# rw-pd1b.net
KiCad netlist of a schematic drawn in EAGLE
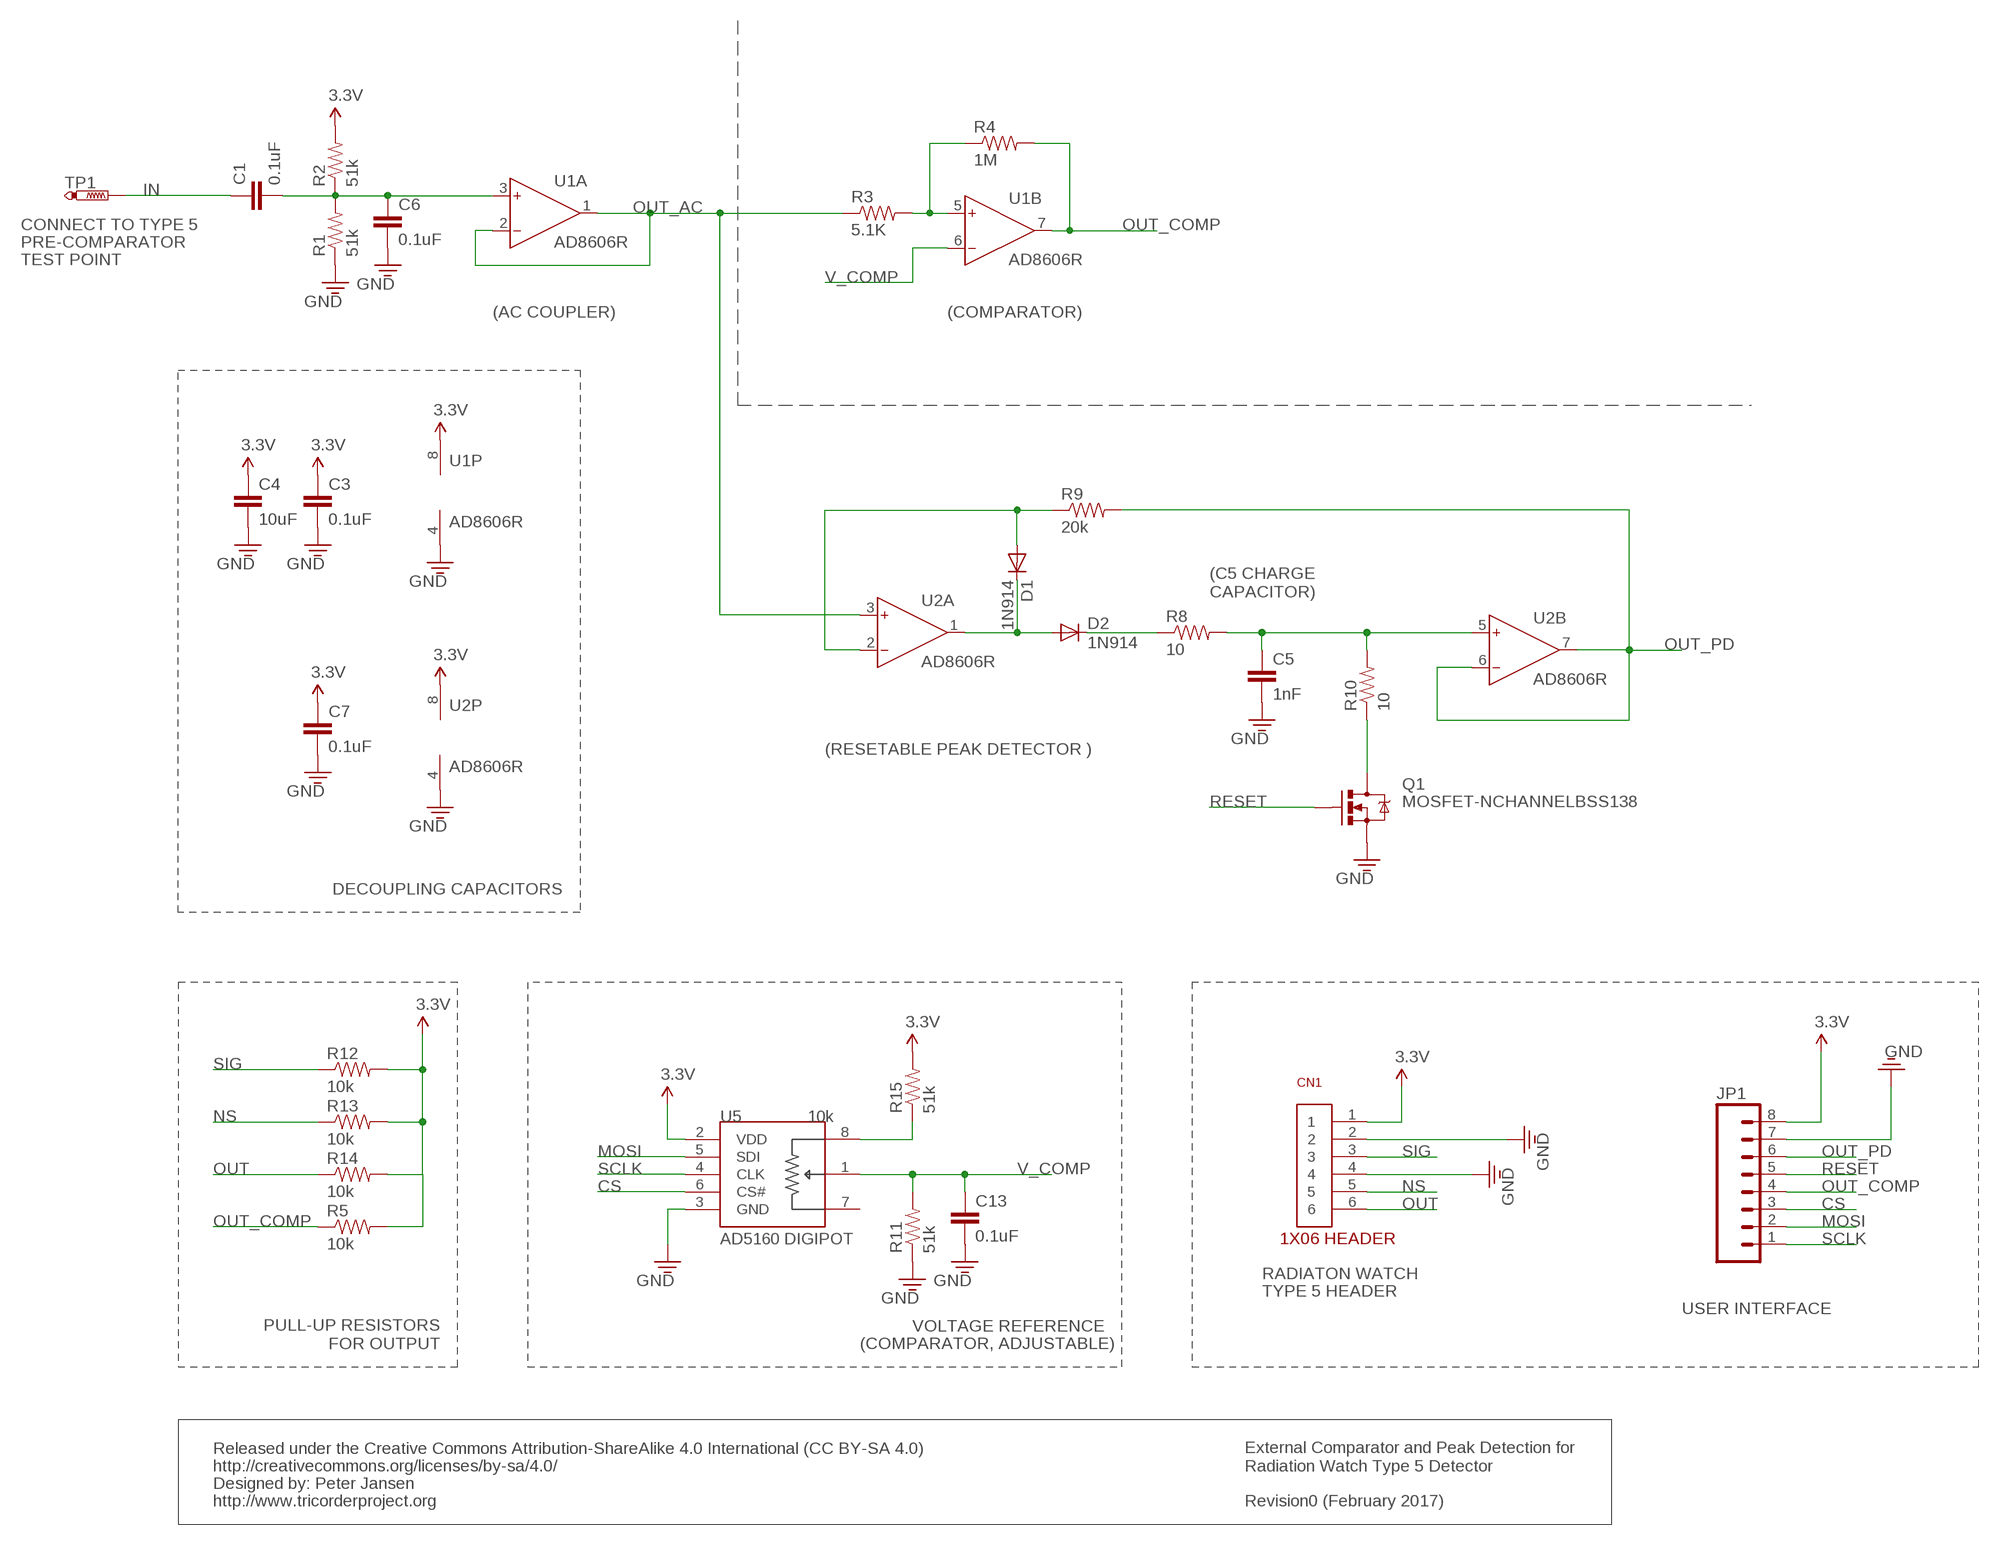
[diagram p0: schematic, sheet 1]

(export (version "E")
  (design (tool "Eeschema 10.0.6"))
  (components
    (comp (ref "C1")
      (value "0.1uF")
      (footprint "eagle-import:0603")
      (libsource (lib "eagle-import") (part "CAP0603"))
    )
    (comp (ref "C3")
      (value "0.1uF")
      (footprint "eagle-import:0603")
      (libsource (lib "eagle-import") (part "CAP0603"))
    )
    (comp (ref "C4")
      (value "10uF")
      (footprint "eagle-import:0603")
      (libsource (lib "eagle-import") (part "CAP0603"))
    )
    (comp (ref "C5")
      (value "1nF")
      (footprint "eagle-import:0603")
      (libsource (lib "eagle-import") (part "CAP0603"))
    )
    (comp (ref "C6")
      (value "0.1uF")
      (footprint "eagle-import:0603")
      (libsource (lib "eagle-import") (part "CAP0603"))
    )
    (comp (ref "C7")
      (value "0.1uF")
      (footprint "eagle-import:0603")
      (libsource (lib "eagle-import") (part "CAP0603"))
    )
    (comp (ref "C13")
      (value "0.1uF")
      (footprint "eagle-import:0603")
      (libsource (lib "eagle-import") (part "openct_CAP0603"))
    )
    (comp (ref "CN1")
      (value "1X06")
      (footprint "eagle-import:1X06")
      (libsource (lib "eagle-import") (part "1X06"))
    )
    (comp (ref "D1")
      (value "1N914")
      (footprint "eagle-import:SOD-323")
      (libsource (lib "eagle-import") (part "DIODESOD"))
    )
    (comp (ref "D2")
      (value "1N914")
      (footprint "eagle-import:SOD-323")
      (libsource (lib "eagle-import") (part "DIODESOD"))
    )
    (comp (ref "JP1")
      (value "M08LOCK")
      (footprint "eagle-import:1X08_LOCK")
      (libsource (lib "eagle-import") (part "M08LOCK"))
    )
    (comp (ref "Q1")
      (value "MOSFET-NCHANNELBSS138")
      (footprint "eagle-import:SOT23")
      (libsource (lib "eagle-import") (part "MOSFET-NCHANNELBSS138"))
    )
    (comp (ref "R1")
      (value "51k")
      (footprint "eagle-import:0603")
      (libsource (lib "eagle-import") (part "RESISTOR0603"))
    )
    (comp (ref "R2")
      (value "51k")
      (footprint "eagle-import:0603")
      (libsource (lib "eagle-import") (part "RESISTOR0603"))
    )
    (comp (ref "R3")
      (value "5.1K")
      (footprint "eagle-import:0603")
      (libsource (lib "eagle-import") (part "RESISTOR0603"))
    )
    (comp (ref "R4")
      (value "1M")
      (footprint "eagle-import:0603")
      (libsource (lib "eagle-import") (part "RESISTOR0603"))
    )
    (comp (ref "R5")
      (value "10k")
      (footprint "eagle-import:0603")
      (libsource (lib "eagle-import") (part "RESISTOR0603"))
    )
    (comp (ref "R8")
      (value "10")
      (footprint "eagle-import:0603")
      (libsource (lib "eagle-import") (part "RESISTOR0603"))
    )
    (comp (ref "R9")
      (value "20k")
      (footprint "eagle-import:0603")
      (libsource (lib "eagle-import") (part "RESISTOR0603"))
    )
    (comp (ref "R10")
      (value "10")
      (footprint "eagle-import:0603")
      (libsource (lib "eagle-import") (part "RESISTOR0603"))
    )
    (comp (ref "R11")
      (value "51k")
      (footprint "eagle-import:0603")
      (libsource (lib "eagle-import") (part "openct_RESISTOR0603"))
    )
    (comp (ref "R12")
      (value "10k")
      (footprint "eagle-import:0603")
      (libsource (lib "eagle-import") (part "RESISTOR0603"))
    )
    (comp (ref "R13")
      (value "10k")
      (footprint "eagle-import:0603")
      (libsource (lib "eagle-import") (part "RESISTOR0603"))
    )
    (comp (ref "R14")
      (value "10k")
      (footprint "eagle-import:0603")
      (libsource (lib "eagle-import") (part "RESISTOR0603"))
    )
    (comp (ref "R15")
      (value "51k")
      (footprint "eagle-import:0603")
      (libsource (lib "eagle-import") (part "openct_RESISTOR0603"))
    )
    (comp (ref "TP1")
      (value "PTR1PAD1-13")
      (footprint "eagle-import:P1-13")
      (libsource (lib "eagle-import") (part "PTR1PAD1-13"))
    )
    (comp (ref "U1")
      (value "AD8606R")
      (footprint "eagle-import:SO8")
      (fields (field (name "MPN") "AD8607ARMZ-R2"))
      (libsource (lib "eagle-import") (part "AD8607R"))
    )
    (comp (ref "U2")
      (value "AD8606R")
      (footprint "eagle-import:SO8")
      (fields (field (name "MPN") "AD8607ARMZ-R2"))
      (libsource (lib "eagle-import") (part "AD8607R"))
    )
    (comp (ref "U5")
      (value "10k")
      (footprint "eagle-import:SOT-23-8")
      (libsource (lib "eagle-import") (part "AD5160"))
    )
  )
  (nets
    (net (code "1") (name "/CS") (class "Default")
      (node (ref "JP1") (pin "3") (pinfunction "3_3") (pintype "passive"))
      (node (ref "U5") (pin "6") (pinfunction "CS#_6") (pintype "bidirectional"))
    )
    (net (code "2") (name "/IN") (class "Default")
      (node (ref "C1") (pin "1") (pinfunction "1_1") (pintype "passive"))
      (node (ref "TP1") (pin "TP") (pinfunction "TP_TP") (pintype "input"))
    )
    (net (code "3") (name "/MOSI") (class "Default")
      (node (ref "JP1") (pin "2") (pinfunction "2_2") (pintype "passive"))
      (node (ref "U5") (pin "5") (pinfunction "SDI_5") (pintype "bidirectional"))
    )
    (net (code "4") (name "/NS") (class "Default")
      (node (ref "CN1") (pin "5") (pinfunction "5_5") (pintype "bidirectional"))
      (node (ref "R13") (pin "1") (pinfunction "1_1") (pintype "passive"))
    )
    (net (code "5") (name "/OUT") (class "Default")
      (node (ref "CN1") (pin "6") (pinfunction "6_6") (pintype "bidirectional"))
      (node (ref "R14") (pin "1") (pinfunction "1_1") (pintype "passive"))
    )
    (net (code "6") (name "/OUT_AC") (class "Default")
      (node (ref "R3") (pin "1") (pinfunction "1_1") (pintype "passive"))
      (node (ref "U1") (pin "1") (pinfunction "OUT_1") (pintype "output"))
      (node (ref "U1") (pin "2") (pinfunction "IN-_2") (pintype "input"))
      (node (ref "U2") (pin "3") (pinfunction "IN+_3") (pintype "input"))
    )
    (net (code "7") (name "/OUT_COMP") (class "Default")
      (node (ref "JP1") (pin "4") (pinfunction "4_4") (pintype "passive"))
      (node (ref "R4") (pin "2") (pinfunction "2_2") (pintype "passive"))
      (node (ref "R5") (pin "1") (pinfunction "1_1") (pintype "passive"))
      (node (ref "U1") (pin "7") (pinfunction "OUT_7") (pintype "output"))
    )
    (net (code "8") (name "/OUT_PD") (class "Default")
      (node (ref "JP1") (pin "6") (pinfunction "6_6") (pintype "passive"))
      (node (ref "R9") (pin "2") (pinfunction "2_2") (pintype "passive"))
      (node (ref "U2") (pin "6") (pinfunction "IN-_6") (pintype "input"))
      (node (ref "U2") (pin "7") (pinfunction "OUT_7") (pintype "output"))
    )
    (net (code "9") (name "/RESET") (class "Default")
      (node (ref "JP1") (pin "5") (pinfunction "5_5") (pintype "passive"))
      (node (ref "Q1") (pin "1") (pinfunction "G_1") (pintype "passive"))
    )
    (net (code "10") (name "/SCLK") (class "Default")
      (node (ref "JP1") (pin "1") (pinfunction "1_1") (pintype "passive"))
      (node (ref "U5") (pin "4") (pinfunction "CLK_4") (pintype "bidirectional"))
    )
    (net (code "11") (name "/SIG") (class "Default")
      (node (ref "CN1") (pin "3") (pinfunction "3_3") (pintype "bidirectional"))
      (node (ref "R12") (pin "1") (pinfunction "1_1") (pintype "passive"))
    )
    (net (code "12") (name "/V_COMP") (class "Default")
      (node (ref "C13") (pin "1") (pinfunction "1_1") (pintype "passive"))
      (node (ref "R11") (pin "2") (pinfunction "2_2") (pintype "passive"))
      (node (ref "U1") (pin "6") (pinfunction "IN-_6") (pintype "input"))
      (node (ref "U5") (pin "1") (pinfunction "W_1") (pintype "bidirectional"))
    )
    (net (code "13") (name "3.3V") (class "Default")
      (node (ref "C3") (pin "1") (pinfunction "1_1") (pintype "passive"))
      (node (ref "C4") (pin "1") (pinfunction "1_1") (pintype "passive"))
      (node (ref "C7") (pin "1") (pinfunction "1_1") (pintype "passive"))
      (node (ref "CN1") (pin "1") (pinfunction "1_1") (pintype "bidirectional"))
      (node (ref "JP1") (pin "8") (pinfunction "8_8") (pintype "passive"))
      (node (ref "R12") (pin "2") (pinfunction "2_2") (pintype "passive"))
      (node (ref "R13") (pin "2") (pinfunction "2_2") (pintype "passive"))
      (node (ref "R14") (pin "2") (pinfunction "2_2") (pintype "passive"))
      (node (ref "R15") (pin "2") (pinfunction "2_2") (pintype "passive"))
      (node (ref "R2") (pin "2") (pinfunction "2_2") (pintype "passive"))
      (node (ref "R5") (pin "2") (pinfunction "2_2") (pintype "passive"))
      (node (ref "U1") (pin "8") (pinfunction "V+_8") (pintype "power_in"))
      (node (ref "U2") (pin "8") (pinfunction "V+_8") (pintype "power_in"))
      (node (ref "U5") (pin "2") (pinfunction "VDD_2") (pintype "bidirectional"))
    )
    (net (code "14") (name "GND") (class "Default")
      (node (ref "C13") (pin "2") (pinfunction "2_2") (pintype "passive"))
      (node (ref "C3") (pin "2") (pinfunction "2_2") (pintype "passive"))
      (node (ref "C4") (pin "2") (pinfunction "2_2") (pintype "passive"))
      (node (ref "C5") (pin "2") (pinfunction "2_2") (pintype "passive"))
      (node (ref "C6") (pin "2") (pinfunction "2_2") (pintype "passive"))
      (node (ref "C7") (pin "2") (pinfunction "2_2") (pintype "passive"))
      (node (ref "CN1") (pin "2") (pinfunction "2_2") (pintype "bidirectional"))
      (node (ref "CN1") (pin "4") (pinfunction "4_4") (pintype "bidirectional"))
      (node (ref "JP1") (pin "7") (pinfunction "7_7") (pintype "passive"))
      (node (ref "Q1") (pin "2") (pinfunction "S_2") (pintype "passive"))
      (node (ref "R1") (pin "1") (pinfunction "1_1") (pintype "passive"))
      (node (ref "R11") (pin "1") (pinfunction "1_1") (pintype "passive"))
      (node (ref "U1") (pin "4") (pinfunction "V-_4") (pintype "power_in"))
      (node (ref "U2") (pin "4") (pinfunction "V-_4") (pintype "power_in"))
      (node (ref "U5") (pin "3") (pinfunction "GND_3") (pintype "bidirectional"))
    )
    (net (code "15") (name "Net-(D2-PadC)") (class "Default")
      (node (ref "D2") (pin "C") (pinfunction "C_C") (pintype "passive"))
      (node (ref "R8") (pin "1") (pinfunction "1_1") (pintype "passive"))
    )
    (net (code "16") (name "Net-(Q1-D)") (class "Default")
      (node (ref "Q1") (pin "3") (pinfunction "D_3") (pintype "passive"))
      (node (ref "R10") (pin "1") (pinfunction "1_1") (pintype "passive"))
    )
    (net (code "17") (name "Net-(U1A-IN+)") (class "Default")
      (node (ref "C1") (pin "2") (pinfunction "2_2") (pintype "passive"))
      (node (ref "C6") (pin "1") (pinfunction "1_1") (pintype "passive"))
      (node (ref "R1") (pin "2") (pinfunction "2_2") (pintype "passive"))
      (node (ref "R2") (pin "1") (pinfunction "1_1") (pintype "passive"))
      (node (ref "U1") (pin "3") (pinfunction "IN+_3") (pintype "input"))
    )
    (net (code "18") (name "Net-(U1B-IN+)") (class "Default")
      (node (ref "R3") (pin "2") (pinfunction "2_2") (pintype "passive"))
      (node (ref "R4") (pin "1") (pinfunction "1_1") (pintype "passive"))
      (node (ref "U1") (pin "5") (pinfunction "IN+_5") (pintype "input"))
    )
    (net (code "19") (name "Net-(U2A-IN-)") (class "Default")
      (node (ref "D1") (pin "A") (pinfunction "A_A") (pintype "passive"))
      (node (ref "R9") (pin "1") (pinfunction "1_1") (pintype "passive"))
      (node (ref "U2") (pin "2") (pinfunction "IN-_2") (pintype "input"))
    )
    (net (code "20") (name "Net-(U2A-OUT)") (class "Default")
      (node (ref "D1") (pin "C") (pinfunction "C_C") (pintype "passive"))
      (node (ref "D2") (pin "A") (pinfunction "A_A") (pintype "passive"))
      (node (ref "U2") (pin "1") (pinfunction "OUT_1") (pintype "output"))
    )
    (net (code "21") (name "Net-(U2B-IN+)") (class "Default")
      (node (ref "C5") (pin "1") (pinfunction "1_1") (pintype "passive"))
      (node (ref "R10") (pin "2") (pinfunction "2_2") (pintype "passive"))
      (node (ref "R8") (pin "2") (pinfunction "2_2") (pintype "passive"))
      (node (ref "U2") (pin "5") (pinfunction "IN+_5") (pintype "input"))
    )
    (net (code "22") (name "Net-(U5-A)") (class "Default")
      (node (ref "R15") (pin "1") (pinfunction "1_1") (pintype "passive"))
      (node (ref "U5") (pin "8") (pinfunction "A_8") (pintype "bidirectional"))
    )
    (net (code "23") (name "unconnected-(U5-B-Pad7)") (class "Default")
      (node (ref "U5") (pin "7") (pinfunction "B_7") (pintype "bidirectional"))
    )
  )
)
